# op-synth.net
KiCad netlist of a schematic drawn in EAGLE
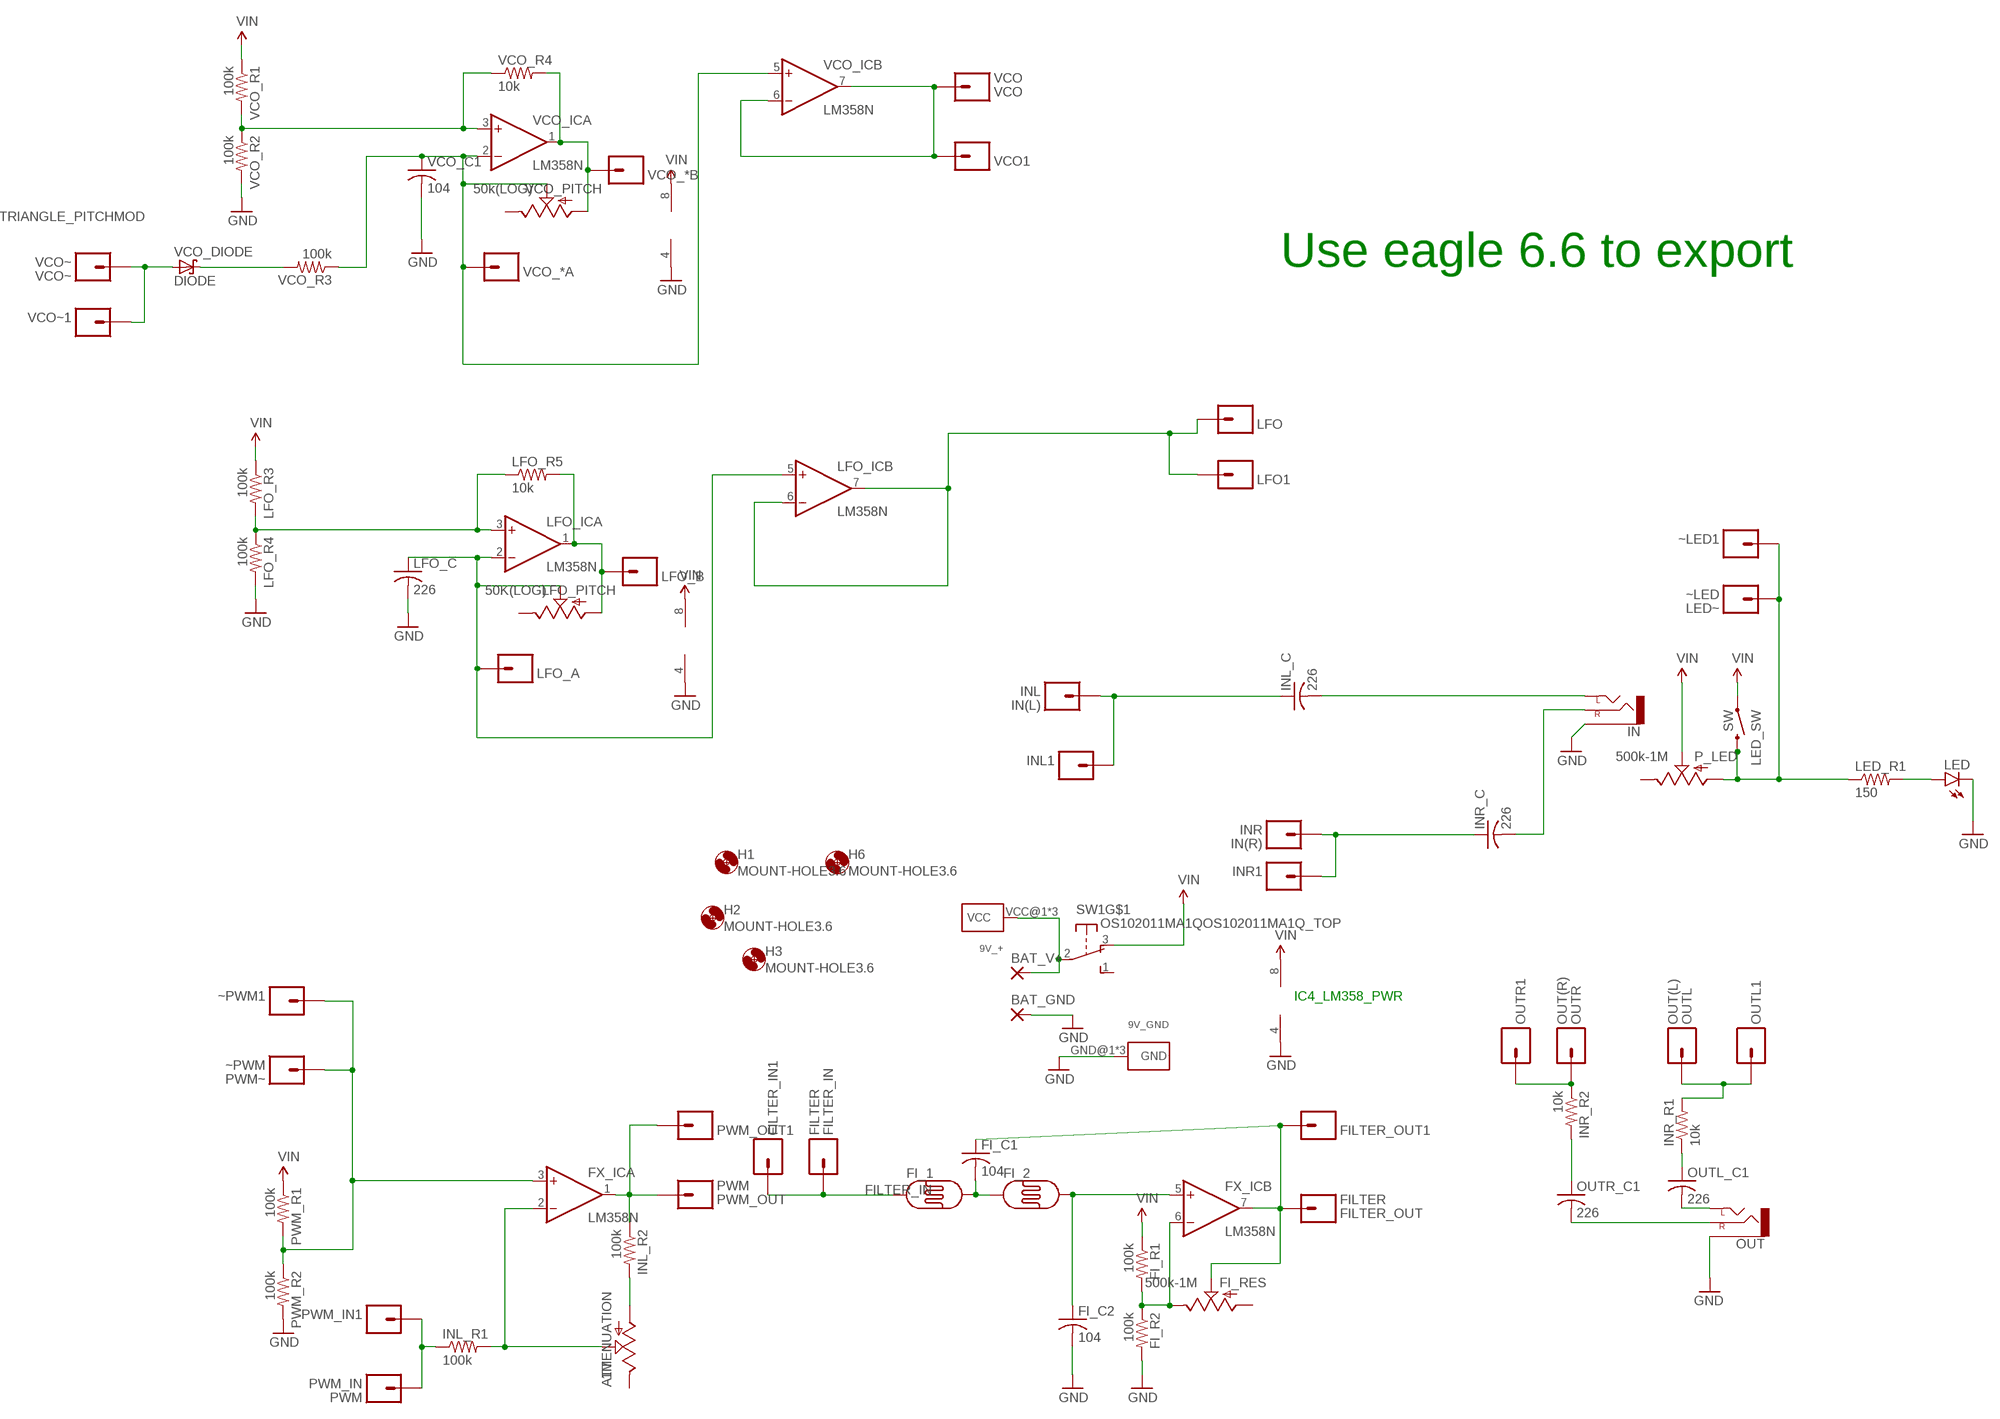
[diagram p0: schematic, sheet 1]

(export (version "E")
  (design (tool "Eeschema 10.0.6"))
  (components
    (comp (ref "9V_+")
      (value "KEYSTONE-637")
      (footprint "eagle-import:KEYSTONE_AA_AAA_BATTERY_TERMINAL-637")
      (libsource (lib "eagle-import") (part "KEYSTONE-637"))
    )
    (comp (ref "9V_GND")
      (value "KEYSTONE-629")
      (footprint "eagle-import:KEYSTONE_AA_AAA_BATTERY_TERMINAL-629")
      (libsource (lib "eagle-import") (part "KEYSTONE-629"))
    )
    (comp (ref "ATTENUATION")
      (value "1M")
      (footprint "eagle-import:TRIM_POT")
      (libsource (lib "eagle-import") (part "POTTRIM"))
    )
    (comp (ref "BAT_GND")
      (value "3,81/1,4")
      (footprint "eagle-import:3,81_1,4")
      (libsource (lib "eagle-import") (part "3,81/1,4"))
    )
    (comp (ref "BAT_V+")
      (value "3,81/1,4")
      (footprint "eagle-import:3,81_1,4")
      (libsource (lib "eagle-import") (part "3,81/1,4"))
    )
    (comp (ref "FILTER_IN")
      (value "FILTER")
      (footprint "eagle-import:1X01_SIDE_NAME")
      (libsource (lib "eagle-import") (part "HEADER-1X1"))
    )
    (comp (ref "FILTER_IN1")
      (value "HEADER-1X1")
      (footprint "eagle-import:1X01_SIDE_NAME")
      (libsource (lib "eagle-import") (part "HEADER-1X1"))
    )
    (comp (ref "FILTER_OUT")
      (value "FILTER")
      (footprint "eagle-import:1X01_SIDE_NAME")
      (libsource (lib "eagle-import") (part "HEADER-1X1"))
    )
    (comp (ref "FILTER_OUT1")
      (value "HEADER-1X1")
      (footprint "eagle-import:1X01_SIDE_NAME")
      (libsource (lib "eagle-import") (part "HEADER-1X1"))
    )
    (comp (ref "FI_1")
      (value "PHOTOCELLPTH")
      (footprint "eagle-import:PHOTOCELL")
      (libsource (lib "eagle-import") (part "PHOTOCELLPTH"))
    )
    (comp (ref "FI_2")
      (value "PHOTOCELLPTH")
      (footprint "eagle-import:PHOTOCELL")
      (libsource (lib "eagle-import") (part "PHOTOCELLPTH"))
    )
    (comp (ref "FI_C1")
      (value "104")
      (footprint "eagle-import:C050-024X044")
      (libsource (lib "eagle-import") (part "resistor_348_C-US050-024X044"))
    )
    (comp (ref "FI_C2")
      (value "104")
      (footprint "eagle-import:C050-024X044")
      (libsource (lib "eagle-import") (part "resistor_348_C-US050-024X044"))
    )
    (comp (ref "FI_R1")
      (value "100k")
      (footprint "eagle-import:0204_7")
      (libsource (lib "eagle-import") (part "R-US_0204/7"))
    )
    (comp (ref "FI_R2")
      (value "100k")
      (footprint "eagle-import:0204_7")
      (libsource (lib "eagle-import") (part "R-US_0204/7"))
    )
    (comp (ref "FI_RES")
      (value "500k-1M")
      (footprint "eagle-import:ALPS_POT")
      (libsource (lib "eagle-import") (part "POT"))
    )
    (comp (ref "FX_IC")
      (value "LM358N")
      (footprint "eagle-import:DIL08")
      (libsource (lib "eagle-import") (part "LM358N"))
    )
    (comp (ref "H1")
      (value "MOUNT-HOLE3.6")
      (footprint "eagle-import:3,6")
      (libsource (lib "eagle-import") (part "MOUNT-HOLE3.6"))
    )
    (comp (ref "H2")
      (value "MOUNT-HOLE3.6")
      (footprint "eagle-import:3,6")
      (libsource (lib "eagle-import") (part "MOUNT-HOLE3.6"))
    )
    (comp (ref "H3")
      (value "MOUNT-HOLE3.6")
      (footprint "eagle-import:3,6")
      (libsource (lib "eagle-import") (part "MOUNT-HOLE3.6"))
    )
    (comp (ref "H6")
      (value "MOUNT-HOLE3.6")
      (footprint "eagle-import:3,6")
      (libsource (lib "eagle-import") (part "MOUNT-HOLE3.6"))
    )
    (comp (ref "IN")
      (value "AUDIO-JACKPTH")
      (footprint "eagle-import:AUDIO-JACK")
      (libsource (lib "eagle-import") (part "AUDIO-JACKPTH"))
    )
    (comp (ref "INL")
      (value "IN(L)")
      (footprint "eagle-import:1X01_SIDE_NAME")
      (libsource (lib "eagle-import") (part "HEADER-1X1"))
    )
    (comp (ref "INL1")
      (value "HEADER-1X1")
      (footprint "eagle-import:1X01_SIDE_NAME")
      (libsource (lib "eagle-import") (part "HEADER-1X1"))
    )
    (comp (ref "INL_C")
      (value "226")
      (footprint "eagle-import:C050-024X044")
      (libsource (lib "eagle-import") (part "C-US050-024X044"))
    )
    (comp (ref "INL_R1")
      (value "100k")
      (footprint "eagle-import:0204_7")
      (libsource (lib "eagle-import") (part "R-US_0204/7"))
    )
    (comp (ref "INL_R2")
      (value "100k")
      (footprint "eagle-import:0204_7")
      (libsource (lib "eagle-import") (part "R-US_0204/7"))
    )
    (comp (ref "INR")
      (value "IN(R)")
      (footprint "eagle-import:1X01_SIDE_NAME")
      (libsource (lib "eagle-import") (part "HEADER-1X1"))
    )
    (comp (ref "INR1")
      (value "HEADER-1X1")
      (footprint "eagle-import:1X01_SIDE_NAME")
      (libsource (lib "eagle-import") (part "HEADER-1X1"))
    )
    (comp (ref "INR_C")
      (value "226")
      (footprint "eagle-import:C050-024X044")
      (libsource (lib "eagle-import") (part "C-US050-024X044"))
    )
    (comp (ref "INR_R1")
      (value "10k")
      (footprint "eagle-import:0204_7")
      (libsource (lib "eagle-import") (part "R-US_0204/7"))
    )
    (comp (ref "INR_R2")
      (value "10k")
      (footprint "eagle-import:0204_7")
      (libsource (lib "eagle-import") (part "R-US_0204/7"))
    )
    (comp (ref "LED")
      (value "LED5MM")
      (footprint "eagle-import:LED5MM")
      (libsource (lib "eagle-import") (part "LED5MM"))
    )
    (comp (ref "LED_R1")
      (value "150")
      (footprint "eagle-import:0204_7")
      (libsource (lib "eagle-import") (part "R-US_0204/7"))
    )
    (comp (ref "LED_SW")
      (value "SW")
      (footprint "eagle-import:TACTILE-PTH-12MM")
      (libsource (lib "eagle-import") (part "SWITCH-MOMENTARY-212MM"))
    )
    (comp (ref "LFO")
      (value "HEADER-1X1")
      (footprint "eagle-import:1X01_SIDE_NAME")
      (libsource (lib "eagle-import") (part "HEADER-1X1"))
    )
    (comp (ref "LFO1")
      (value "HEADER-1X1")
      (footprint "eagle-import:1X01_SIDE_NAME")
      (libsource (lib "eagle-import") (part "HEADER-1X1"))
    )
    (comp (ref "LFO_A")
      (value "HEADER-1X1")
      (footprint "eagle-import:1X01_SIDE_NAME")
      (libsource (lib "eagle-import") (part "HEADER-1X1"))
    )
    (comp (ref "LFO_B")
      (value "HEADER-1X1")
      (footprint "eagle-import:1X01_SIDE_NAME")
      (libsource (lib "eagle-import") (part "HEADER-1X1"))
    )
    (comp (ref "LFO_C")
      (value "226")
      (footprint "eagle-import:C050-024X044")
      (libsource (lib "eagle-import") (part "resistor_348_C-US050-024X044"))
    )
    (comp (ref "LFO_IC")
      (value "LM358N")
      (footprint "eagle-import:DIL08")
      (libsource (lib "eagle-import") (part "LM358N"))
    )
    (comp (ref "LFO_PITCH")
      (value "50K(LOG)")
      (footprint "eagle-import:ALPS_POT")
      (libsource (lib "eagle-import") (part "POT"))
    )
    (comp (ref "LFO_R3")
      (value "100k")
      (footprint "eagle-import:0204_7")
      (libsource (lib "eagle-import") (part "R-US_0204/7"))
    )
    (comp (ref "LFO_R4")
      (value "100k")
      (footprint "eagle-import:0204_7")
      (libsource (lib "eagle-import") (part "R-US_0204/7"))
    )
    (comp (ref "LFO_R5")
      (value "10k")
      (footprint "eagle-import:0204_7")
      (libsource (lib "eagle-import") (part "R-US_0204/7"))
    )
    (comp (ref "OUT")
      (value "AUDIO-JACKPTH")
      (footprint "eagle-import:AUDIO-JACK")
      (libsource (lib "eagle-import") (part "AUDIO-JACKPTH"))
    )
    (comp (ref "OUTL")
      (value "OUT(L)")
      (footprint "eagle-import:1X01_SIDE_NAME")
      (libsource (lib "eagle-import") (part "HEADER-1X1"))
    )
    (comp (ref "OUTL1")
      (value "HEADER-1X1")
      (footprint "eagle-import:1X01_SIDE_NAME")
      (libsource (lib "eagle-import") (part "HEADER-1X1"))
    )
    (comp (ref "OUTL_C1")
      (value "226")
      (footprint "eagle-import:C050-024X044")
      (libsource (lib "eagle-import") (part "C-US050-024X044"))
    )
    (comp (ref "OUTR")
      (value "OUT(R)")
      (footprint "eagle-import:1X01_SIDE_NAME")
      (libsource (lib "eagle-import") (part "HEADER-1X1"))
    )
    (comp (ref "OUTR1")
      (value "HEADER-1X1")
      (footprint "eagle-import:1X01_SIDE_NAME")
      (libsource (lib "eagle-import") (part "HEADER-1X1"))
    )
    (comp (ref "OUTR_C1")
      (value "226")
      (footprint "eagle-import:C050-024X044")
      (libsource (lib "eagle-import") (part "C-US050-024X044"))
    )
    (comp (ref "PWM_IN")
      (value "PWM")
      (footprint "eagle-import:1X01_SIDE_NAME")
      (libsource (lib "eagle-import") (part "HEADER-1X1"))
    )
    (comp (ref "PWM_IN1")
      (value "HEADER-1X1")
      (footprint "eagle-import:1X01_SIDE_NAME")
      (libsource (lib "eagle-import") (part "HEADER-1X1"))
    )
    (comp (ref "PWM_OUT")
      (value "PWM")
      (footprint "eagle-import:1X01_SIDE_NAME")
      (libsource (lib "eagle-import") (part "HEADER-1X1"))
    )
    (comp (ref "PWM_OUT1")
      (value "HEADER-1X1")
      (footprint "eagle-import:1X01_SIDE_NAME")
      (libsource (lib "eagle-import") (part "HEADER-1X1"))
    )
    (comp (ref "PWM_R1")
      (value "100k")
      (footprint "eagle-import:0204_7")
      (libsource (lib "eagle-import") (part "R-US_0204/7"))
    )
    (comp (ref "PWM_R2")
      (value "100k")
      (footprint "eagle-import:0204_7")
      (libsource (lib "eagle-import") (part "R-US_0204/7"))
    )
    (comp (ref "P_LED")
      (value "500k-1M")
      (footprint "eagle-import:ALPS_POT")
      (libsource (lib "eagle-import") (part "POT"))
    )
    (comp (ref "SW1")
      (value "OS102011MA1QOS102011MA1Q_TOP")
      (footprint "eagle-import:OS102011MA1Q")
      (libsource (lib "eagle-import") (part "OS102011MA1QOS102011MA1Q_TOP"))
    )
    (comp (ref "VCO")
      (value "VCO")
      (footprint "eagle-import:1X01_SIDE_NAME")
      (libsource (lib "eagle-import") (part "HEADER-1X1"))
    )
    (comp (ref "VCO1")
      (value "HEADER-1X1")
      (footprint "eagle-import:1X01_SIDE_NAME")
      (libsource (lib "eagle-import") (part "HEADER-1X1"))
    )
    (comp (ref "VCO_*A")
      (value "HEADER-1X1")
      (footprint "eagle-import:1X01_SIDE_NAME")
      (libsource (lib "eagle-import") (part "HEADER-1X1"))
    )
    (comp (ref "VCO_*B")
      (value "HEADER-1X1")
      (footprint "eagle-import:1X01_SIDE_NAME")
      (libsource (lib "eagle-import") (part "HEADER-1X1"))
    )
    (comp (ref "VCO_C1")
      (value "104")
      (footprint "eagle-import:C050-024X044")
      (libsource (lib "eagle-import") (part "C-US050-024X044"))
    )
    (comp (ref "VCO_DIODE")
      (value "DIODE")
      (footprint "eagle-import:DO41-7")
      (libsource (lib "eagle-import") (part "SCHOTTKY-DIODEDO41-7"))
    )
    (comp (ref "VCO_IC")
      (value "LM358N")
      (footprint "eagle-import:DIL08")
      (libsource (lib "eagle-import") (part "LM358N"))
    )
    (comp (ref "VCO_PITCH")
      (value "50k(LOG)")
      (footprint "eagle-import:ALPS_POT")
      (libsource (lib "eagle-import") (part "POT"))
    )
    (comp (ref "VCO_R1")
      (value "100k")
      (footprint "eagle-import:0204_7")
      (libsource (lib "eagle-import") (part "R-US_0204/7"))
    )
    (comp (ref "VCO_R2")
      (value "100k")
      (footprint "eagle-import:0204_7")
      (libsource (lib "eagle-import") (part "R-US_0204/7"))
    )
    (comp (ref "VCO_R3")
      (value "100k")
      (footprint "eagle-import:0204_7")
      (libsource (lib "eagle-import") (part "R-US_0204/7"))
    )
    (comp (ref "VCO_R4")
      (value "10k")
      (footprint "eagle-import:0204_7")
      (libsource (lib "eagle-import") (part "R-US_0204/7"))
    )
    (comp (ref "VCO~")
      (value "VCO~")
      (footprint "eagle-import:1X01_SIDE_NAME")
      (libsource (lib "eagle-import") (part "HEADER-1X1"))
    )
    (comp (ref "VCO~1")
      (value "HEADER-1X1")
      (footprint "eagle-import:1X01_SIDE_NAME")
      (libsource (lib "eagle-import") (part "HEADER-1X1"))
    )
    (comp (ref "~LED")
      (value "LED~")
      (footprint "eagle-import:1X01_SIDE_NAME")
      (libsource (lib "eagle-import") (part "HEADER-1X1"))
    )
    (comp (ref "~LED1")
      (value "HEADER-1X1")
      (footprint "eagle-import:1X01_SIDE_NAME")
      (libsource (lib "eagle-import") (part "HEADER-1X1"))
    )
    (comp (ref "~PWM")
      (value "PWM~")
      (footprint "eagle-import:1X01_SIDE_NAME")
      (libsource (lib "eagle-import") (part "HEADER-1X1"))
    )
    (comp (ref "~PWM1")
      (value "HEADER-1X1")
      (footprint "eagle-import:1X01_SIDE_NAME")
      (libsource (lib "eagle-import") (part "HEADER-1X1"))
    )
  )
  (nets
    (net (code "1") (name "/FILTER_IN") (class "Default")
      (node (ref "FILTER_IN") (pin "1") (pinfunction "1_1") (pintype "passive"))
      (node (ref "FILTER_IN1") (pin "1") (pinfunction "1_1") (pintype "passive"))
      (node (ref "FI_1") (pin "1") (pinfunction "P$1_1") (pintype "bidirectional"))
    )
    (net (code "2") (name "/TRIANGLE_PITCHMOD") (class "Default")
      (node (ref "VCO_DIODE") (pin "A") (pinfunction "A_A") (pintype "passive"))
      (node (ref "VCO~") (pin "1") (pinfunction "1_1") (pintype "passive"))
      (node (ref "VCO~1") (pin "1") (pinfunction "1_1") (pintype "passive"))
    )
    (net (code "3") (name "GND") (class "Default")
      (node (ref "9V_GND") (pin "GND@1") (pinfunction "GND_GND@1") (pintype "power_in"))
      (node (ref "9V_GND") (pin "GND@2") (pinfunction "GND_GND@2") (pintype "power_in"))
      (node (ref "9V_GND") (pin "GND@3") (pinfunction "GND_GND@3") (pintype "power_in"))
      (node (ref "BAT_GND") (pin "1") (pinfunction "P_1") (pintype "passive"))
      (node (ref "FI_C2") (pin "2") (pinfunction "2_2") (pintype "passive"))
      (node (ref "FI_R2") (pin "2") (pinfunction "2_2") (pintype "passive"))
      (node (ref "FX_IC") (pin "4") (pinfunction "V-_4") (pintype "power_in"))
      (node (ref "IN") (pin "SLEEVE") (pinfunction "SLEEVE_SLEEVE") (pintype "bidirectional"))
      (node (ref "LED") (pin "K") (pinfunction "C_K") (pintype "passive"))
      (node (ref "LFO_C") (pin "2") (pinfunction "2_2") (pintype "passive"))
      (node (ref "LFO_IC") (pin "4") (pinfunction "V-_4") (pintype "power_in"))
      (node (ref "LFO_R4") (pin "2") (pinfunction "2_2") (pintype "passive"))
      (node (ref "OUT") (pin "SLEEVE") (pinfunction "SLEEVE_SLEEVE") (pintype "bidirectional"))
      (node (ref "PWM_R2") (pin "2") (pinfunction "2_2") (pintype "passive"))
      (node (ref "VCO_C1") (pin "2") (pinfunction "2_2") (pintype "passive"))
      (node (ref "VCO_IC") (pin "4") (pinfunction "V-_4") (pintype "power_in"))
      (node (ref "VCO_R2") (pin "2") (pinfunction "2_2") (pintype "passive"))
    )
    (net (code "4") (name "Net-(ATTENUATION-A)") (class "Default")
      (node (ref "ATTENUATION") (pin "3") (pinfunction "A_3") (pintype "passive"))
      (node (ref "INL_R2") (pin "2") (pinfunction "2_2") (pintype "passive"))
    )
    (net (code "5") (name "Net-(ATTENUATION-S)") (class "Default")
      (node (ref "ATTENUATION") (pin "1") (pinfunction "S_1") (pintype "passive"))
      (node (ref "FX_IC") (pin "2") (pinfunction "-IN_2") (pintype "input"))
      (node (ref "INL_R1") (pin "2") (pinfunction "2_2") (pintype "passive"))
    )
    (net (code "6") (name "Net-(BAT_V+-P)") (class "Default")
      (node (ref "9V_+") (pin "VCC@1") (pinfunction "VCC_VCC@1") (pintype "power_in"))
      (node (ref "9V_+") (pin "VCC@2") (pinfunction "VCC_VCC@2") (pintype "power_in"))
      (node (ref "9V_+") (pin "VCC@3") (pinfunction "VCC_VCC@3") (pintype "power_in"))
      (node (ref "BAT_V+") (pin "1") (pinfunction "P_1") (pintype "passive"))
      (node (ref "SW1") (pin "2") (pinfunction "P_2") (pintype "passive"))
    )
    (net (code "7") (name "Net-(FI_1-P$2)") (class "Default")
      (node (ref "FI_1") (pin "2") (pinfunction "P$2_2") (pintype "bidirectional"))
      (node (ref "FI_2") (pin "1") (pinfunction "P$1_1") (pintype "bidirectional"))
      (node (ref "FI_C1") (pin "2") (pinfunction "2_2") (pintype "passive"))
    )
    (net (code "8") (name "Net-(FI_2-P$2)") (class "Default")
      (node (ref "FI_2") (pin "2") (pinfunction "P$2_2") (pintype "bidirectional"))
      (node (ref "FI_C2") (pin "1") (pinfunction "1_1") (pintype "passive"))
      (node (ref "FX_IC") (pin "5") (pinfunction "+IN_5") (pintype "input"))
    )
    (net (code "9") (name "Net-(FI_RES-E)") (class "Default")
      (node (ref "FI_R1") (pin "2") (pinfunction "2_2") (pintype "passive"))
      (node (ref "FI_R2") (pin "1") (pinfunction "1_1") (pintype "passive"))
      (node (ref "FI_RES") (pin "P$1") (pinfunction "E_P$1") (pintype "passive"))
      (node (ref "FX_IC") (pin "6") (pinfunction "-IN_6") (pintype "input"))
    )
    (net (code "10") (name "Net-(FI_RES-S)") (class "Default")
      (node (ref "FILTER_OUT") (pin "1") (pinfunction "1_1") (pintype "passive"))
      (node (ref "FILTER_OUT1") (pin "1") (pinfunction "1_1") (pintype "passive"))
      (node (ref "FI_C1") (pin "1") (pinfunction "1_1") (pintype "passive"))
      (node (ref "FI_RES") (pin "P$2") (pinfunction "S_P$2") (pintype "passive"))
      (node (ref "FX_IC") (pin "7") (pinfunction "OUT_7") (pintype "output"))
    )
    (net (code "11") (name "Net-(FX_ICA-+IN)") (class "Default")
      (node (ref "FX_IC") (pin "3") (pinfunction "+IN_3") (pintype "input"))
      (node (ref "PWM_R1") (pin "2") (pinfunction "2_2") (pintype "passive"))
      (node (ref "PWM_R2") (pin "1") (pinfunction "1_1") (pintype "passive"))
      (node (ref "~PWM") (pin "1") (pinfunction "1_1") (pintype "passive"))
      (node (ref "~PWM1") (pin "1") (pinfunction "1_1") (pintype "passive"))
    )
    (net (code "12") (name "Net-(FX_ICA-OUT)") (class "Default")
      (node (ref "FX_IC") (pin "1") (pinfunction "OUT_1") (pintype "output"))
      (node (ref "INL_R2") (pin "1") (pinfunction "1_1") (pintype "passive"))
      (node (ref "PWM_OUT") (pin "1") (pinfunction "1_1") (pintype "passive"))
      (node (ref "PWM_OUT1") (pin "1") (pinfunction "1_1") (pintype "passive"))
    )
    (net (code "13") (name "Net-(IN-LEFT)") (class "Default")
      (node (ref "IN") (pin "TIP") (pinfunction "LEFT_TIP") (pintype "bidirectional"))
      (node (ref "INL_C") (pin "2") (pinfunction "2_2") (pintype "passive"))
    )
    (net (code "14") (name "Net-(IN-RIGHT)") (class "Default")
      (node (ref "IN") (pin "RING") (pinfunction "RIGHT_RING") (pintype "bidirectional"))
      (node (ref "INR_C") (pin "2") (pinfunction "2_2") (pintype "passive"))
    )
    (net (code "15") (name "Net-(INL-Pad1)") (class "Default")
      (node (ref "INL") (pin "1") (pinfunction "1_1") (pintype "passive"))
      (node (ref "INL1") (pin "1") (pinfunction "1_1") (pintype "passive"))
      (node (ref "INL_C") (pin "1") (pinfunction "1_1") (pintype "passive"))
    )
    (net (code "16") (name "Net-(INL_R1-Pad1)") (class "Default")
      (node (ref "INL_R1") (pin "1") (pinfunction "1_1") (pintype "passive"))
      (node (ref "PWM_IN") (pin "1") (pinfunction "1_1") (pintype "passive"))
      (node (ref "PWM_IN1") (pin "1") (pinfunction "1_1") (pintype "passive"))
    )
    (net (code "17") (name "Net-(INR-Pad1)") (class "Default")
      (node (ref "INR") (pin "1") (pinfunction "1_1") (pintype "passive"))
      (node (ref "INR1") (pin "1") (pinfunction "1_1") (pintype "passive"))
      (node (ref "INR_C") (pin "1") (pinfunction "1_1") (pintype "passive"))
    )
    (net (code "18") (name "Net-(INR_R1-Pad1)") (class "Default")
      (node (ref "INR_R1") (pin "1") (pinfunction "1_1") (pintype "passive"))
      (node (ref "OUTL_C1") (pin "1") (pinfunction "1_1") (pintype "passive"))
    )
    (net (code "19") (name "Net-(INR_R1-Pad2)") (class "Default")
      (node (ref "INR_R1") (pin "2") (pinfunction "2_2") (pintype "passive"))
      (node (ref "OUTL") (pin "1") (pinfunction "1_1") (pintype "passive"))
      (node (ref "OUTL1") (pin "1") (pinfunction "1_1") (pintype "passive"))
    )
    (net (code "20") (name "Net-(INR_R2-Pad1)") (class "Default")
      (node (ref "INR_R2") (pin "1") (pinfunction "1_1") (pintype "passive"))
      (node (ref "OUTR") (pin "1") (pinfunction "1_1") (pintype "passive"))
      (node (ref "OUTR1") (pin "1") (pinfunction "1_1") (pintype "passive"))
    )
    (net (code "21") (name "Net-(INR_R2-Pad2)") (class "Default")
      (node (ref "INR_R2") (pin "2") (pinfunction "2_2") (pintype "passive"))
      (node (ref "OUTR_C1") (pin "1") (pinfunction "1_1") (pintype "passive"))
    )
    (net (code "22") (name "Net-(LED-PadA)") (class "Default")
      (node (ref "LED") (pin "A") (pinfunction "A_A") (pintype "passive"))
      (node (ref "LED_R1") (pin "2") (pinfunction "2_2") (pintype "passive"))
    )
    (net (code "23") (name "Net-(LED_SW-2)") (class "Default")
      (node (ref "LED_R1") (pin "1") (pinfunction "1_1") (pintype "passive"))
      (node (ref "LED_SW") (pin "3") (pinfunction "2_3") (pintype "passive"))
      (node (ref "P_LED") (pin "P$3") (pinfunction "A_P$3") (pintype "passive"))
      (node (ref "~LED") (pin "1") (pinfunction "1_1") (pintype "passive"))
      (node (ref "~LED1") (pin "1") (pinfunction "1_1") (pintype "passive"))
    )
    (net (code "24") (name "Net-(LFO_ICA-+IN)") (class "Default")
      (node (ref "LFO_IC") (pin "3") (pinfunction "+IN_3") (pintype "input"))
      (node (ref "LFO_R3") (pin "2") (pinfunction "2_2") (pintype "passive"))
      (node (ref "LFO_R4") (pin "1") (pinfunction "1_1") (pintype "passive"))
      (node (ref "LFO_R5") (pin "1") (pinfunction "1_1") (pintype "passive"))
    )
    (net (code "25") (name "Net-(LFO_ICA--IN)") (class "Default")
      (node (ref "LFO_A") (pin "1") (pinfunction "1_1") (pintype "passive"))
      (node (ref "LFO_C") (pin "1") (pinfunction "1_1") (pintype "passive"))
      (node (ref "LFO_IC") (pin "2") (pinfunction "-IN_2") (pintype "input"))
      (node (ref "LFO_IC") (pin "5") (pinfunction "+IN_5") (pintype "input"))
      (node (ref "LFO_PITCH") (pin "P$2") (pinfunction "S_P$2") (pintype "passive"))
    )
    (net (code "26") (name "Net-(LFO_ICA-OUT)") (class "Default")
      (node (ref "LFO_B") (pin "1") (pinfunction "1_1") (pintype "passive"))
      (node (ref "LFO_IC") (pin "1") (pinfunction "OUT_1") (pintype "output"))
      (node (ref "LFO_PITCH") (pin "P$3") (pinfunction "A_P$3") (pintype "passive"))
      (node (ref "LFO_R5") (pin "2") (pinfunction "2_2") (pintype "passive"))
    )
    (net (code "27") (name "Net-(LFO_ICB--IN)") (class "Default")
      (node (ref "LFO") (pin "1") (pinfunction "1_1") (pintype "passive"))
      (node (ref "LFO1") (pin "1") (pinfunction "1_1") (pintype "passive"))
      (node (ref "LFO_IC") (pin "6") (pinfunction "-IN_6") (pintype "input"))
      (node (ref "LFO_IC") (pin "7") (pinfunction "OUT_7") (pintype "output"))
    )
    (net (code "28") (name "Net-(OUT-LEFT)") (class "Default")
      (node (ref "OUT") (pin "TIP") (pinfunction "LEFT_TIP") (pintype "bidirectional"))
      (node (ref "OUTL_C1") (pin "2") (pinfunction "2_2") (pintype "passive"))
    )
    (net (code "29") (name "Net-(OUT-RIGHT)") (class "Default")
      (node (ref "OUT") (pin "RING") (pinfunction "RIGHT_RING") (pintype "bidirectional"))
      (node (ref "OUTR_C1") (pin "2") (pinfunction "2_2") (pintype "passive"))
    )
    (net (code "30") (name "Net-(VCO_DIODE-PadC)") (class "Default")
      (node (ref "VCO_DIODE") (pin "C") (pinfunction "C_C") (pintype "passive"))
      (node (ref "VCO_R3") (pin "2") (pinfunction "2_2") (pintype "passive"))
    )
    (net (code "31") (name "Net-(VCO_ICA-+IN)") (class "Default")
      (node (ref "VCO_IC") (pin "3") (pinfunction "+IN_3") (pintype "input"))
      (node (ref "VCO_R1") (pin "2") (pinfunction "2_2") (pintype "passive"))
      (node (ref "VCO_R2") (pin "1") (pinfunction "1_1") (pintype "passive"))
      (node (ref "VCO_R4") (pin "1") (pinfunction "1_1") (pintype "passive"))
    )
    (net (code "32") (name "Net-(VCO_ICA--IN)") (class "Default")
      (node (ref "VCO_*A") (pin "1") (pinfunction "1_1") (pintype "passive"))
      (node (ref "VCO_C1") (pin "1") (pinfunction "1_1") (pintype "passive"))
      (node (ref "VCO_IC") (pin "2") (pinfunction "-IN_2") (pintype "input"))
      (node (ref "VCO_IC") (pin "5") (pinfunction "+IN_5") (pintype "input"))
      (node (ref "VCO_PITCH") (pin "P$2") (pinfunction "S_P$2") (pintype "passive"))
      (node (ref "VCO_R3") (pin "1") (pinfunction "1_1") (pintype "passive"))
    )
    (net (code "33") (name "Net-(VCO_ICA-OUT)") (class "Default")
      (node (ref "VCO_*B") (pin "1") (pinfunction "1_1") (pintype "passive"))
      (node (ref "VCO_IC") (pin "1") (pinfunction "OUT_1") (pintype "output"))
      (node (ref "VCO_PITCH") (pin "P$3") (pinfunction "A_P$3") (pintype "passive"))
      (node (ref "VCO_R4") (pin "2") (pinfunction "2_2") (pintype "passive"))
    )
    (net (code "34") (name "Net-(VCO_ICB--IN)") (class "Default")
      (node (ref "VCO") (pin "1") (pinfunction "1_1") (pintype "passive"))
      (node (ref "VCO1") (pin "1") (pinfunction "1_1") (pintype "passive"))
      (node (ref "VCO_IC") (pin "6") (pinfunction "-IN_6") (pintype "input"))
      (node (ref "VCO_IC") (pin "7") (pinfunction "OUT_7") (pintype "output"))
    )
    (net (code "35") (name "VIN") (class "Default")
      (node (ref "FI_R1") (pin "1") (pinfunction "1_1") (pintype "passive"))
      (node (ref "FX_IC") (pin "8") (pinfunction "V+_8") (pintype "power_in"))
      (node (ref "LED_SW") (pin "1") (pinfunction "1_1") (pintype "passive"))
      (node (ref "LFO_IC") (pin "8") (pinfunction "V+_8") (pintype "power_in"))
      (node (ref "LFO_R3") (pin "1") (pinfunction "1_1") (pintype "passive"))
      (node (ref "PWM_R1") (pin "1") (pinfunction "1_1") (pintype "passive"))
      (node (ref "P_LED") (pin "P$2") (pinfunction "S_P$2") (pintype "passive"))
      (node (ref "SW1") (pin "3") (pinfunction "O_3") (pintype "passive"))
      (node (ref "VCO_IC") (pin "8") (pinfunction "V+_8") (pintype "power_in"))
      (node (ref "VCO_R1") (pin "1") (pinfunction "1_1") (pintype "passive"))
    )
    (net (code "36") (name "unconnected-(ATTENUATION-E-Pad2)") (class "Default")
      (node (ref "ATTENUATION") (pin "2") (pinfunction "E_2") (pintype "passive"))
    )
    (net (code "37") (name "unconnected-(FI_RES-A-PadP$3)") (class "Default")
      (node (ref "FI_RES") (pin "P$3") (pinfunction "A_P$3") (pintype "passive"))
    )
    (net (code "38") (name "unconnected-(LFO_PITCH-E-PadP$1)") (class "Default")
      (node (ref "LFO_PITCH") (pin "P$1") (pinfunction "E_P$1") (pintype "passive"))
    )
    (net (code "39") (name "unconnected-(P_LED-E-PadP$1)") (class "Default")
      (node (ref "P_LED") (pin "P$1") (pinfunction "E_P$1") (pintype "passive"))
    )
    (net (code "40") (name "unconnected-(SW1A-S-Pad1)") (class "Default")
      (node (ref "SW1") (pin "1") (pinfunction "S_1") (pintype "passive"))
    )
    (net (code "41") (name "unconnected-(VCO_PITCH-E-PadP$1)") (class "Default")
      (node (ref "VCO_PITCH") (pin "P$1") (pinfunction "E_P$1") (pintype "passive"))
    )
  )
)
